# I2C_buttons_shematic.net
KiCad netlist of a schematic drawn in EAGLE
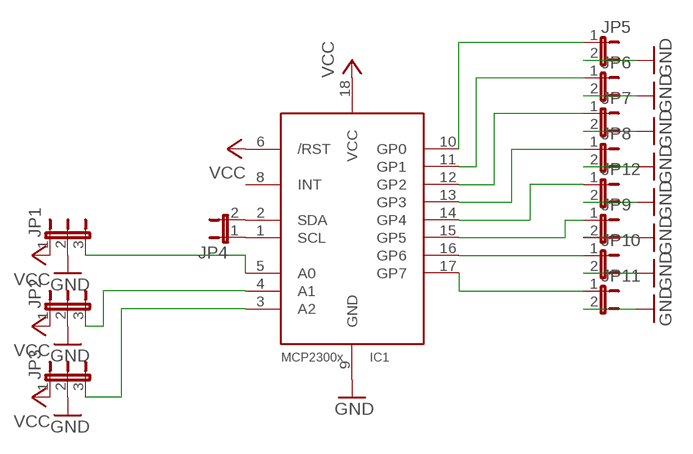
[diagram p0: schematic, sheet 1]

(export (version "E")
  (design (tool "Eeschema 10.0.6"))
  (components
    (comp (ref "IC1")
      (value "MCP23008/P")
      (footprint "eagle-import:DIL18")
      (libsource (lib "eagle-import") (part "MCP23008/P"))
    )
    (comp (ref "JP1")
      (value "JP2E")
      (footprint "eagle-import:JP2")
      (libsource (lib "eagle-import") (part "JP2E"))
    )
    (comp (ref "JP2")
      (value "JP2E")
      (footprint "eagle-import:JP2")
      (libsource (lib "eagle-import") (part "JP2E"))
    )
    (comp (ref "JP3")
      (value "JP2E")
      (footprint "eagle-import:JP2")
      (libsource (lib "eagle-import") (part "JP2E"))
    )
    (comp (ref "JP4")
      (value "JP1E")
      (footprint "eagle-import:JP1")
      (libsource (lib "eagle-import") (part "JP1E"))
    )
    (comp (ref "JP5")
      (value "JP1E")
      (footprint "eagle-import:JP1")
      (libsource (lib "eagle-import") (part "JP1E"))
    )
    (comp (ref "JP6")
      (value "JP1E")
      (footprint "eagle-import:JP1")
      (libsource (lib "eagle-import") (part "JP1E"))
    )
    (comp (ref "JP7")
      (value "JP1E")
      (footprint "eagle-import:JP1")
      (libsource (lib "eagle-import") (part "JP1E"))
    )
    (comp (ref "JP8")
      (value "JP1E")
      (footprint "eagle-import:JP1")
      (libsource (lib "eagle-import") (part "JP1E"))
    )
    (comp (ref "JP9")
      (value "JP1E")
      (footprint "eagle-import:JP1")
      (libsource (lib "eagle-import") (part "JP1E"))
    )
    (comp (ref "JP10")
      (value "JP1E")
      (footprint "eagle-import:JP1")
      (libsource (lib "eagle-import") (part "JP1E"))
    )
    (comp (ref "JP11")
      (value "JP1E")
      (footprint "eagle-import:JP1")
      (libsource (lib "eagle-import") (part "JP1E"))
    )
    (comp (ref "JP12")
      (value "JP1E")
      (footprint "eagle-import:JP1")
      (libsource (lib "eagle-import") (part "JP1E"))
    )
  )
  (nets
    (net (code "1") (name "GND") (class "Default")
      (node (ref "IC1") (pin "9") (pinfunction "GND_9") (pintype "power_in"))
      (node (ref "JP1") (pin "2") (pinfunction "2_2") (pintype "passive"))
      (node (ref "JP10") (pin "2") (pinfunction "2_2") (pintype "passive"))
      (node (ref "JP11") (pin "2") (pinfunction "2_2") (pintype "passive"))
      (node (ref "JP12") (pin "2") (pinfunction "2_2") (pintype "passive"))
      (node (ref "JP2") (pin "2") (pinfunction "2_2") (pintype "passive"))
      (node (ref "JP3") (pin "2") (pinfunction "2_2") (pintype "passive"))
      (node (ref "JP5") (pin "2") (pinfunction "2_2") (pintype "passive"))
      (node (ref "JP6") (pin "2") (pinfunction "2_2") (pintype "passive"))
      (node (ref "JP7") (pin "2") (pinfunction "2_2") (pintype "passive"))
      (node (ref "JP8") (pin "2") (pinfunction "2_2") (pintype "passive"))
      (node (ref "JP9") (pin "2") (pinfunction "2_2") (pintype "passive"))
    )
    (net (code "2") (name "Net-(IC1-A0)") (class "Default")
      (node (ref "IC1") (pin "5") (pinfunction "A0_5") (pintype "input"))
      (node (ref "JP1") (pin "3") (pinfunction "3_3") (pintype "passive"))
    )
    (net (code "3") (name "Net-(IC1-A1)") (class "Default")
      (node (ref "IC1") (pin "4") (pinfunction "A1_4") (pintype "input"))
      (node (ref "JP2") (pin "3") (pinfunction "3_3") (pintype "passive"))
    )
    (net (code "4") (name "Net-(IC1-A2)") (class "Default")
      (node (ref "IC1") (pin "3") (pinfunction "A2_3") (pintype "input"))
      (node (ref "JP3") (pin "3") (pinfunction "3_3") (pintype "passive"))
    )
    (net (code "5") (name "Net-(IC1-GP0)") (class "Default")
      (node (ref "IC1") (pin "10") (pinfunction "GP0_10") (pintype "bidirectional"))
      (node (ref "JP5") (pin "1") (pinfunction "1_1") (pintype "passive"))
    )
    (net (code "6") (name "Net-(IC1-GP1)") (class "Default")
      (node (ref "IC1") (pin "11") (pinfunction "GP1_11") (pintype "bidirectional"))
      (node (ref "JP6") (pin "1") (pinfunction "1_1") (pintype "passive"))
    )
    (net (code "7") (name "Net-(IC1-GP2)") (class "Default")
      (node (ref "IC1") (pin "12") (pinfunction "GP2_12") (pintype "bidirectional"))
      (node (ref "JP7") (pin "1") (pinfunction "1_1") (pintype "passive"))
    )
    (net (code "8") (name "Net-(IC1-GP3)") (class "Default")
      (node (ref "IC1") (pin "13") (pinfunction "GP3_13") (pintype "bidirectional"))
      (node (ref "JP8") (pin "1") (pinfunction "1_1") (pintype "passive"))
    )
    (net (code "9") (name "Net-(IC1-GP4)") (class "Default")
      (node (ref "IC1") (pin "14") (pinfunction "GP4_14") (pintype "bidirectional"))
      (node (ref "JP12") (pin "1") (pinfunction "1_1") (pintype "passive"))
    )
    (net (code "10") (name "Net-(IC1-GP5)") (class "Default")
      (node (ref "IC1") (pin "15") (pinfunction "GP5_15") (pintype "bidirectional"))
      (node (ref "JP9") (pin "1") (pinfunction "1_1") (pintype "passive"))
    )
    (net (code "11") (name "Net-(IC1-GP6)") (class "Default")
      (node (ref "IC1") (pin "16") (pinfunction "GP6_16") (pintype "bidirectional"))
      (node (ref "JP10") (pin "1") (pinfunction "1_1") (pintype "passive"))
    )
    (net (code "12") (name "Net-(IC1-GP7)") (class "Default")
      (node (ref "IC1") (pin "17") (pinfunction "GP7_17") (pintype "bidirectional"))
      (node (ref "JP11") (pin "1") (pinfunction "1_1") (pintype "passive"))
    )
    (net (code "13") (name "Net-(IC1-SCL)") (class "Default")
      (node (ref "IC1") (pin "1") (pinfunction "SCL_1") (pintype "bidirectional"))
      (node (ref "JP4") (pin "1") (pinfunction "1_1") (pintype "passive"))
    )
    (net (code "14") (name "Net-(IC1-SDA)") (class "Default")
      (node (ref "IC1") (pin "2") (pinfunction "SDA_2") (pintype "bidirectional"))
      (node (ref "JP4") (pin "2") (pinfunction "2_2") (pintype "passive"))
    )
    (net (code "15") (name "VCC") (class "Default")
      (node (ref "IC1") (pin "18") (pinfunction "VCC_18") (pintype "power_in"))
      (node (ref "IC1") (pin "6") (pinfunction "/RST_6") (pintype "input"))
      (node (ref "JP1") (pin "1") (pinfunction "1_1") (pintype "passive"))
      (node (ref "JP2") (pin "1") (pinfunction "1_1") (pintype "passive"))
      (node (ref "JP3") (pin "1") (pinfunction "1_1") (pintype "passive"))
    )
    (net (code "16") (name "unconnected-(IC1-INT-Pad8)") (class "Default")
      (node (ref "IC1") (pin "8") (pinfunction "INT_8") (pintype "output"))
    )
  )
)
